# MyoWare_Cable_Shield.net
KiCad netlist of a schematic drawn in EAGLE
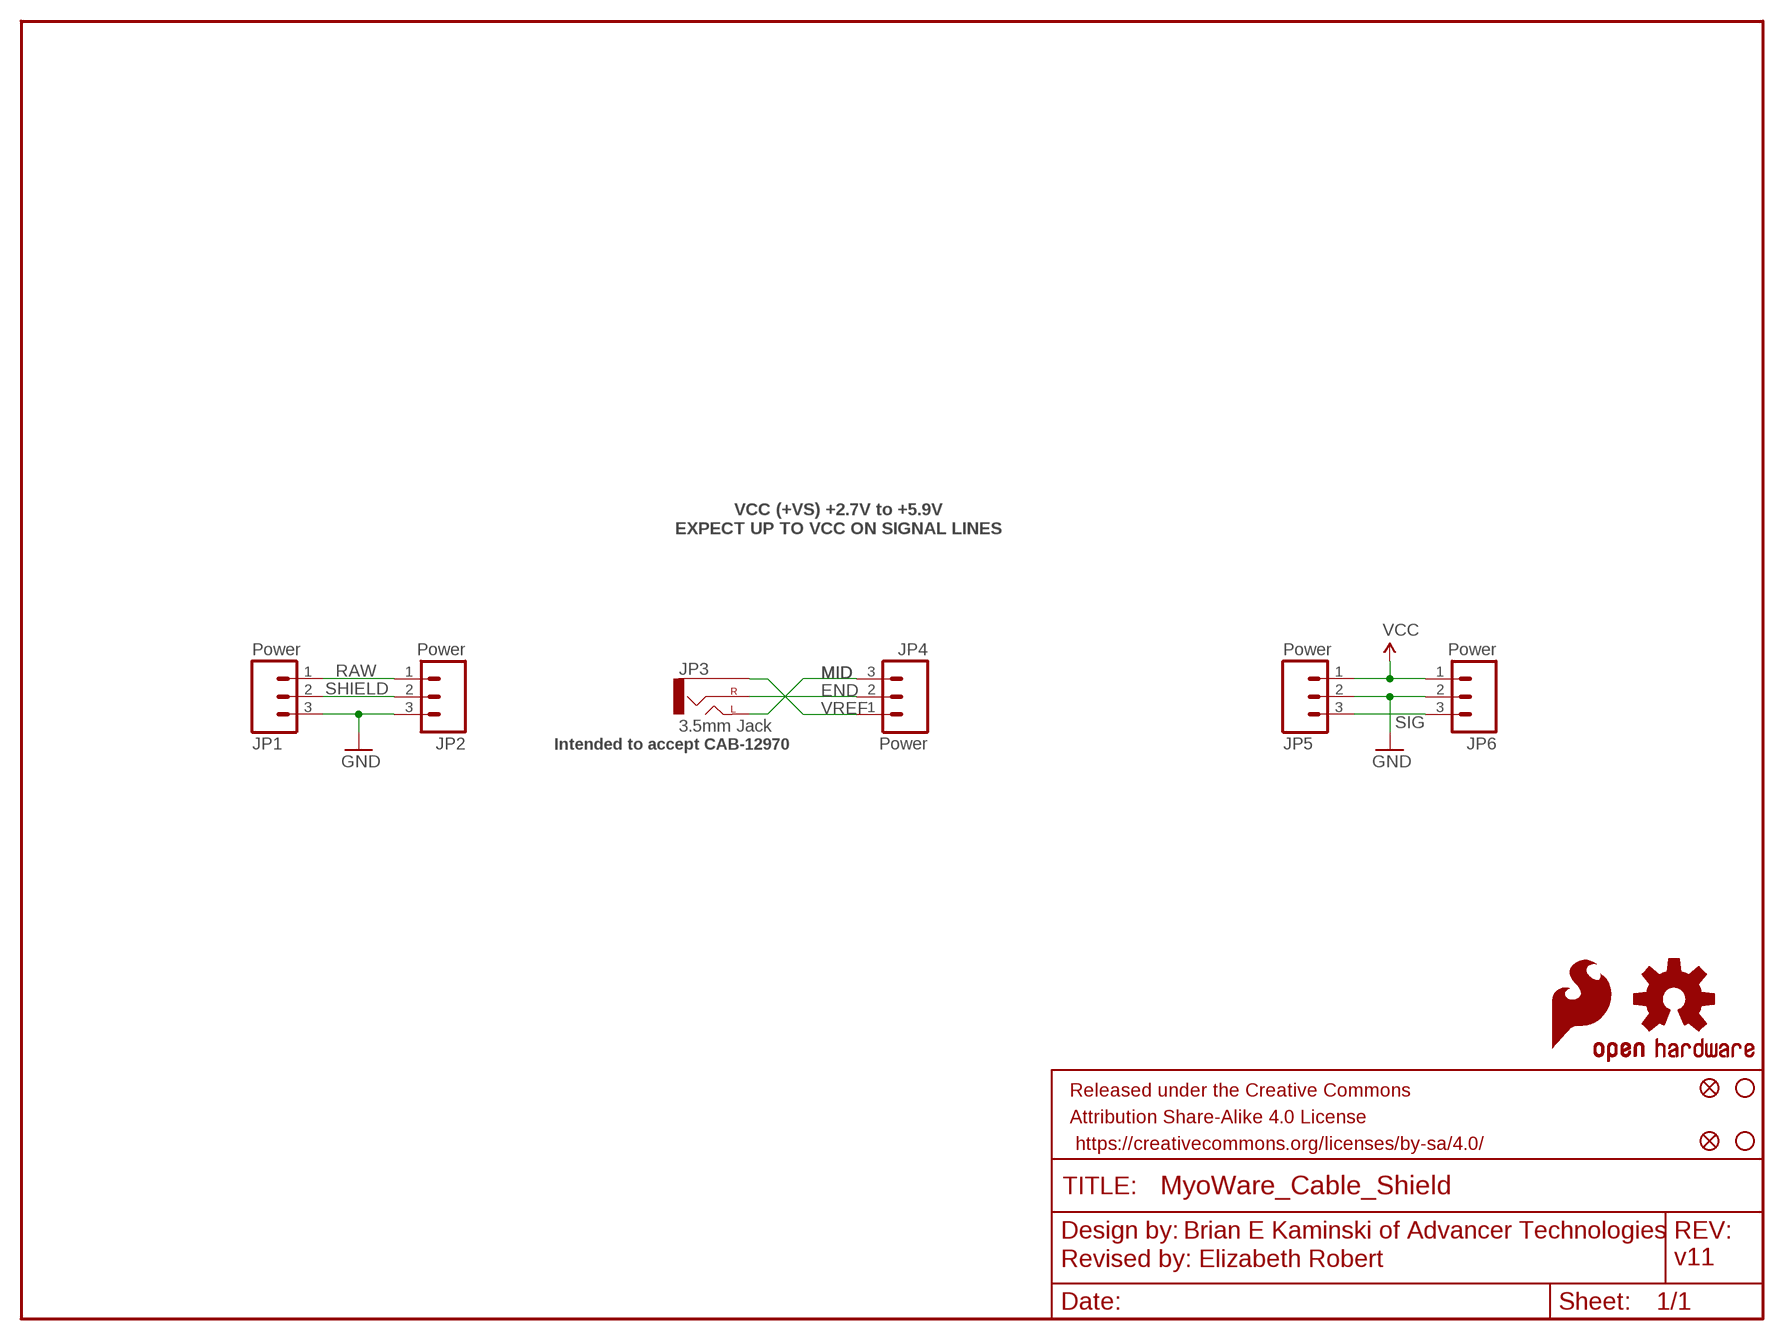
[diagram p0: schematic, sheet 1]

(export (version "E")
  (design (tool "Eeschema 10.0.6"))
  (components
    (comp (ref "FID1")
      (value "FIDUCIAL1X2")
      (footprint "eagle-import:FIDUCIAL-1X2")
      (libsource (lib "eagle-import") (part "FIDUCIAL1X2"))
    )
    (comp (ref "FID2")
      (value "FIDUCIAL1X2")
      (footprint "eagle-import:FIDUCIAL-1X2")
      (libsource (lib "eagle-import") (part "FIDUCIAL1X2"))
    )
    (comp (ref "FRAME1")
      (value "FRAME-LETTER")
      (footprint "eagle-import:CREATIVE_COMMONS")
      (libsource (lib "eagle-import") (part "FRAME-LETTER"))
    )
    (comp (ref "JP1")
      (value "Power")
      (footprint "eagle-import:1X03_NO_SILK")
      (libsource (lib "eagle-import") (part "M031X03_NO_SILK"))
    )
    (comp (ref "JP2")
      (value "Power")
      (footprint "eagle-import:1X03_NO_SILK")
      (libsource (lib "eagle-import") (part "M031X03_NO_SILK"))
    )
    (comp (ref "JP3")
      (value "3.5mm Jack")
      (footprint "eagle-import:AUDIO-JACK-3.5MM-SMD")
      (libsource (lib "eagle-import") (part "AUDIO-JACKSMD2"))
    )
    (comp (ref "JP4")
      (value "Power")
      (footprint "eagle-import:1X03_NO_SILK")
      (libsource (lib "eagle-import") (part "M031X03_NO_SILK"))
    )
    (comp (ref "JP5")
      (value "Power")
      (footprint "eagle-import:1X03_NO_SILK")
      (libsource (lib "eagle-import") (part "M031X03_NO_SILK"))
    )
    (comp (ref "JP6")
      (value "Power")
      (footprint "eagle-import:1X03_NO_SILK")
      (libsource (lib "eagle-import") (part "M031X03_NO_SILK"))
    )
    (comp (ref "LOGO1")
      (value "SFE_LOGO_FLAME.2_INCH")
      (footprint "eagle-import:SFE_LOGO_FLAME_.2")
      (libsource (lib "eagle-import") (part "SFE_LOGO_FLAME.2_INCH"))
    )
    (comp (ref "LOGO2")
      (value "OSHW-LOGOM")
      (footprint "eagle-import:OSHW-LOGO-M")
      (libsource (lib "eagle-import") (part "OSHW-LOGOM"))
    )
    (comp (ref "STANDOFF1")
      (value "STAND-OFF")
      (footprint "eagle-import:STAND-OFF")
      (libsource (lib "eagle-import") (part "STAND-OFF"))
    )
    (comp (ref "STANDOFF2")
      (value "STAND-OFF")
      (footprint "eagle-import:STAND-OFF")
      (libsource (lib "eagle-import") (part "STAND-OFF"))
    )
  )
  (nets
    (net (code "1") (name "/END") (class "Default")
      (node (ref "JP3") (pin "RING") (pinfunction "RIGHT_RING") (pintype "bidirectional"))
      (node (ref "JP4") (pin "2") (pinfunction "2_2") (pintype "passive"))
    )
    (net (code "2") (name "/MID") (class "Default")
      (node (ref "JP3") (pin "TIP") (pinfunction "LEFT_TIP") (pintype "bidirectional"))
      (node (ref "JP4") (pin "3") (pinfunction "3_3") (pintype "passive"))
    )
    (net (code "3") (name "/RAW") (class "Default")
      (node (ref "JP1") (pin "1") (pinfunction "1_1") (pintype "passive"))
      (node (ref "JP2") (pin "1") (pinfunction "1_1") (pintype "passive"))
    )
    (net (code "4") (name "/SHIELD") (class "Default")
      (node (ref "JP1") (pin "2") (pinfunction "2_2") (pintype "passive"))
      (node (ref "JP2") (pin "2") (pinfunction "2_2") (pintype "passive"))
    )
    (net (code "5") (name "/SIG") (class "Default")
      (node (ref "JP5") (pin "3") (pinfunction "3_3") (pintype "passive"))
      (node (ref "JP6") (pin "3") (pinfunction "3_3") (pintype "passive"))
    )
    (net (code "6") (name "/VREF") (class "Default")
      (node (ref "JP3") (pin "SLEEVE") (pinfunction "SLEEVE_SLEEVE") (pintype "bidirectional"))
      (node (ref "JP4") (pin "1") (pinfunction "1_1") (pintype "passive"))
    )
    (net (code "7") (name "GND") (class "Default")
      (node (ref "JP1") (pin "3") (pinfunction "3_3") (pintype "passive"))
      (node (ref "JP2") (pin "3") (pinfunction "3_3") (pintype "passive"))
      (node (ref "JP5") (pin "2") (pinfunction "2_2") (pintype "passive"))
      (node (ref "JP6") (pin "2") (pinfunction "2_2") (pintype "passive"))
    )
    (net (code "8") (name "VCC") (class "Default")
      (node (ref "JP5") (pin "1") (pinfunction "1_1") (pintype "passive"))
      (node (ref "JP6") (pin "1") (pinfunction "1_1") (pintype "passive"))
    )
  )
)
